# base2-polygon.net
KiCad netlist of a schematic drawn in EAGLE
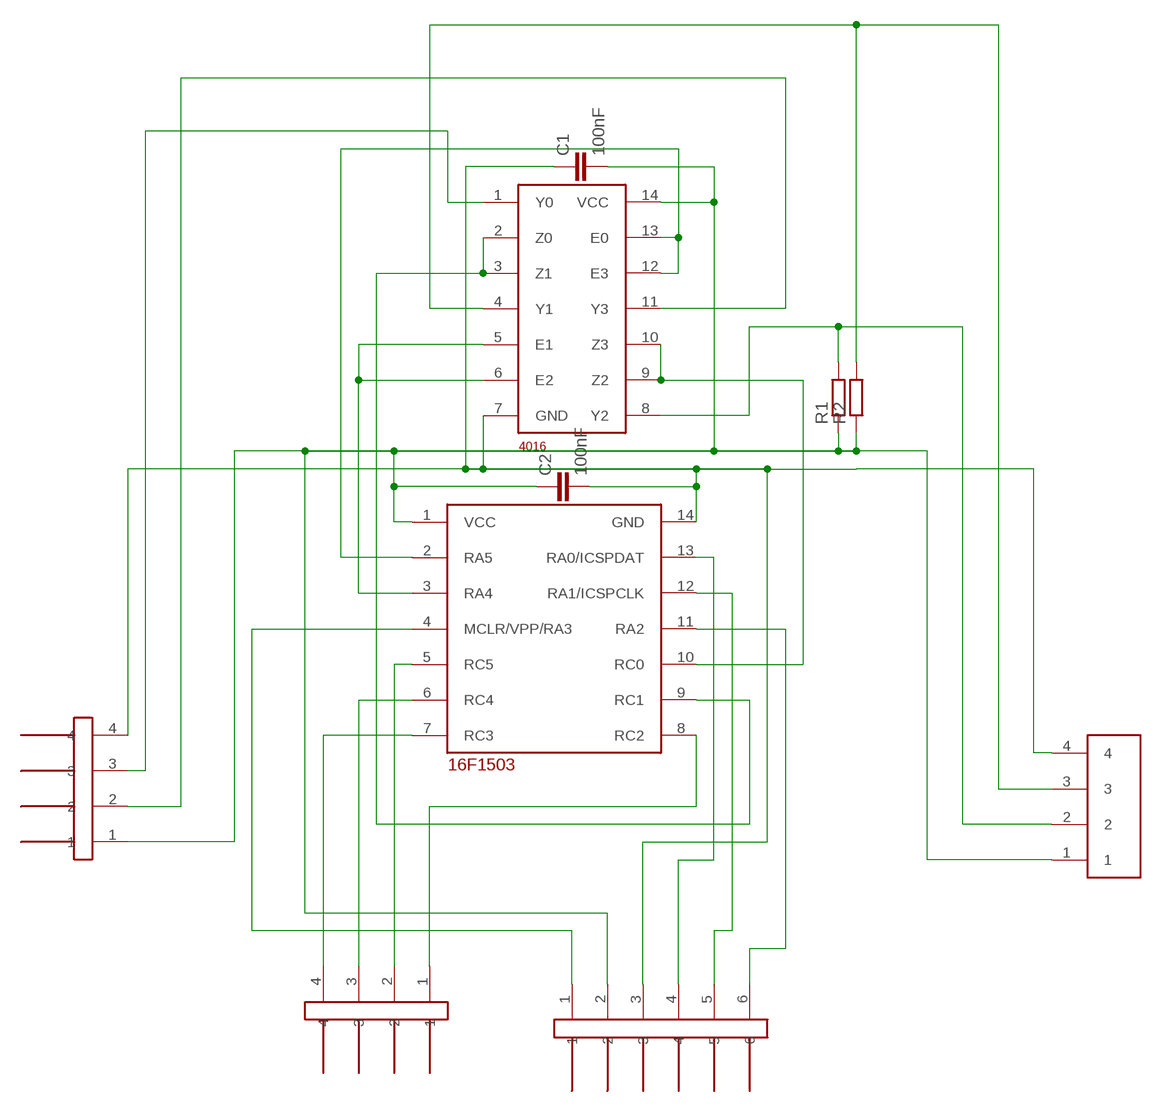
[diagram p0: schematic, sheet 1]

(export (version "E")
  (design (tool "Eeschema 10.0.6"))
  (components
    (comp (ref "C1")
      (value "100nF")
      (footprint "eagle-import:C0805")
      (libsource (lib "eagle-import") (part "C-EUC0805"))
    )
    (comp (ref "C2")
      (value "100nF")
      (footprint "eagle-import:C0805")
      (libsource (lib "eagle-import") (part "C-EUC0805"))
    )
    (comp (ref "INPUT")
      (value "JUMPER4")
      (footprint "eagle-import:JUMPER4")
      (libsource (lib "eagle-import") (part "JUMPER4"))
    )
    (comp (ref "IO")
      (value "JUMPER4M")
      (footprint "eagle-import:JUMPER4M")
      (libsource (lib "eagle-import") (part "JUMPER4M"))
    )
    (comp (ref "OUTPUT")
      (value "JUMPER4F")
      (footprint "eagle-import:JUMPER4F")
      (libsource (lib "eagle-import") (part "JUMPER4F"))
    )
    (comp (ref "PROGRAMMER")
      (value "JUMPER6M")
      (footprint "eagle-import:JUMPER6M")
      (libsource (lib "eagle-import") (part "JUMPER6M"))
    )
    (comp (ref "R1")
      (value "R-EU_M0805")
      (footprint "eagle-import:M0805")
      (libsource (lib "eagle-import") (part "R-EU_M0805"))
    )
    (comp (ref "R2")
      (value "R-EU_M0805")
      (footprint "eagle-import:M0805")
      (libsource (lib "eagle-import") (part "R-EU_M0805"))
    )
    (comp (ref "U$1")
      (value "16F1503")
      (footprint "eagle-import:16F1503")
      (libsource (lib "eagle-import") (part "16F1503"))
    )
    (comp (ref "U$2")
      (value "4016")
      (footprint "eagle-import:4016")
      (libsource (lib "eagle-import") (part "4016"))
    )
  )
  (nets
    (net (code "1") (name "Net-(U$1-GND)") (class "Default")
      (node (ref "C1") (pin "1") (pinfunction "1_1") (pintype "passive"))
      (node (ref "C2") (pin "2") (pinfunction "2_2") (pintype "passive"))
      (node (ref "INPUT") (pin "4") (pinfunction "4_4") (pintype "bidirectional"))
      (node (ref "OUTPUT") (pin "4") (pinfunction "4_4") (pintype "bidirectional"))
      (node (ref "PROGRAMMER") (pin "3") (pinfunction "3_3") (pintype "bidirectional"))
      (node (ref "U$1") (pin "14") (pinfunction "GND_14") (pintype "power_in"))
      (node (ref "U$2") (pin "7") (pinfunction "GND_7") (pintype "bidirectional"))
    )
    (net (code "2") (name "Net-(U$1-MCLR{slash}VPP{slash}RA3)") (class "Default")
      (node (ref "PROGRAMMER") (pin "1") (pinfunction "1_1") (pintype "bidirectional"))
      (node (ref "U$1") (pin "4") (pinfunction "MCLR/VPP/RA3_4") (pintype "bidirectional"))
    )
    (net (code "3") (name "Net-(U$1-RA0{slash}ICSPDAT)") (class "Default")
      (node (ref "PROGRAMMER") (pin "4") (pinfunction "4_4") (pintype "bidirectional"))
      (node (ref "U$1") (pin "13") (pinfunction "RA0/ICSPDAT_13") (pintype "bidirectional"))
    )
    (net (code "4") (name "Net-(U$1-RA1{slash}ICSPCLK)") (class "Default")
      (node (ref "PROGRAMMER") (pin "5") (pinfunction "5_5") (pintype "bidirectional"))
      (node (ref "U$1") (pin "12") (pinfunction "RA1/ICSPCLK_12") (pintype "bidirectional"))
    )
    (net (code "5") (name "Net-(U$1-RA2)") (class "Default")
      (node (ref "PROGRAMMER") (pin "6") (pinfunction "6_6") (pintype "bidirectional"))
      (node (ref "U$1") (pin "11") (pinfunction "RA2_11") (pintype "bidirectional"))
    )
    (net (code "6") (name "Net-(U$1-RA4)") (class "Default")
      (node (ref "U$1") (pin "3") (pinfunction "RA4_3") (pintype "bidirectional"))
      (node (ref "U$2") (pin "5") (pinfunction "E1_5") (pintype "bidirectional"))
      (node (ref "U$2") (pin "6") (pinfunction "E2_6") (pintype "bidirectional"))
    )
    (net (code "7") (name "Net-(U$1-RA5)") (class "Default")
      (node (ref "U$1") (pin "2") (pinfunction "RA5_2") (pintype "bidirectional"))
      (node (ref "U$2") (pin "12") (pinfunction "E3_12") (pintype "bidirectional"))
      (node (ref "U$2") (pin "13") (pinfunction "E0_13") (pintype "bidirectional"))
    )
    (net (code "8") (name "Net-(U$1-RC0)") (class "Default")
      (node (ref "U$1") (pin "10") (pinfunction "RC0_10") (pintype "bidirectional"))
      (node (ref "U$2") (pin "10") (pinfunction "Z3_10") (pintype "bidirectional"))
      (node (ref "U$2") (pin "9") (pinfunction "Z2_9") (pintype "bidirectional"))
    )
    (net (code "9") (name "Net-(U$1-RC1)") (class "Default")
      (node (ref "U$1") (pin "9") (pinfunction "RC1_9") (pintype "bidirectional"))
      (node (ref "U$2") (pin "2") (pinfunction "Z0_2") (pintype "bidirectional"))
      (node (ref "U$2") (pin "3") (pinfunction "Z1_3") (pintype "bidirectional"))
    )
    (net (code "10") (name "Net-(U$1-RC2)") (class "Default")
      (node (ref "IO") (pin "1") (pinfunction "1_1") (pintype "bidirectional"))
      (node (ref "U$1") (pin "8") (pinfunction "RC2_8") (pintype "bidirectional"))
    )
    (net (code "11") (name "Net-(U$1-RC3)") (class "Default")
      (node (ref "IO") (pin "4") (pinfunction "4_4") (pintype "bidirectional"))
      (node (ref "U$1") (pin "7") (pinfunction "RC3_7") (pintype "bidirectional"))
    )
    (net (code "12") (name "Net-(U$1-RC4)") (class "Default")
      (node (ref "IO") (pin "3") (pinfunction "3_3") (pintype "bidirectional"))
      (node (ref "U$1") (pin "6") (pinfunction "RC4_6") (pintype "bidirectional"))
    )
    (net (code "13") (name "Net-(U$1-RC5)") (class "Default")
      (node (ref "IO") (pin "2") (pinfunction "2_2") (pintype "bidirectional"))
      (node (ref "U$1") (pin "5") (pinfunction "RC5_5") (pintype "bidirectional"))
    )
    (net (code "14") (name "Net-(U$1-VCC)") (class "Default")
      (node (ref "C1") (pin "2") (pinfunction "2_2") (pintype "passive"))
      (node (ref "C2") (pin "1") (pinfunction "1_1") (pintype "passive"))
      (node (ref "INPUT") (pin "1") (pinfunction "1_1") (pintype "bidirectional"))
      (node (ref "OUTPUT") (pin "1") (pinfunction "1_1") (pintype "bidirectional"))
      (node (ref "PROGRAMMER") (pin "2") (pinfunction "2_2") (pintype "bidirectional"))
      (node (ref "R1") (pin "1") (pinfunction "1_1") (pintype "passive"))
      (node (ref "R2") (pin "1") (pinfunction "1_1") (pintype "passive"))
      (node (ref "U$1") (pin "1") (pinfunction "VCC_1") (pintype "power_in"))
      (node (ref "U$2") (pin "14") (pinfunction "VCC_14") (pintype "bidirectional"))
    )
    (net (code "15") (name "Net-(U$2-Y0)") (class "Default")
      (node (ref "INPUT") (pin "3") (pinfunction "3_3") (pintype "bidirectional"))
      (node (ref "U$2") (pin "1") (pinfunction "Y0_1") (pintype "bidirectional"))
    )
    (net (code "16") (name "Net-(U$2-Y1)") (class "Default")
      (node (ref "OUTPUT") (pin "3") (pinfunction "3_3") (pintype "bidirectional"))
      (node (ref "R2") (pin "2") (pinfunction "2_2") (pintype "passive"))
      (node (ref "U$2") (pin "4") (pinfunction "Y1_4") (pintype "bidirectional"))
    )
    (net (code "17") (name "Net-(U$2-Y2)") (class "Default")
      (node (ref "OUTPUT") (pin "2") (pinfunction "2_2") (pintype "bidirectional"))
      (node (ref "R1") (pin "2") (pinfunction "2_2") (pintype "passive"))
      (node (ref "U$2") (pin "8") (pinfunction "Y2_8") (pintype "bidirectional"))
    )
    (net (code "18") (name "Net-(U$2-Y3)") (class "Default")
      (node (ref "INPUT") (pin "2") (pinfunction "2_2") (pintype "bidirectional"))
      (node (ref "U$2") (pin "11") (pinfunction "Y3_11") (pintype "bidirectional"))
    )
  )
)
